# Page_2.net
KiCad netlist of a schematic drawn in Altium Designer
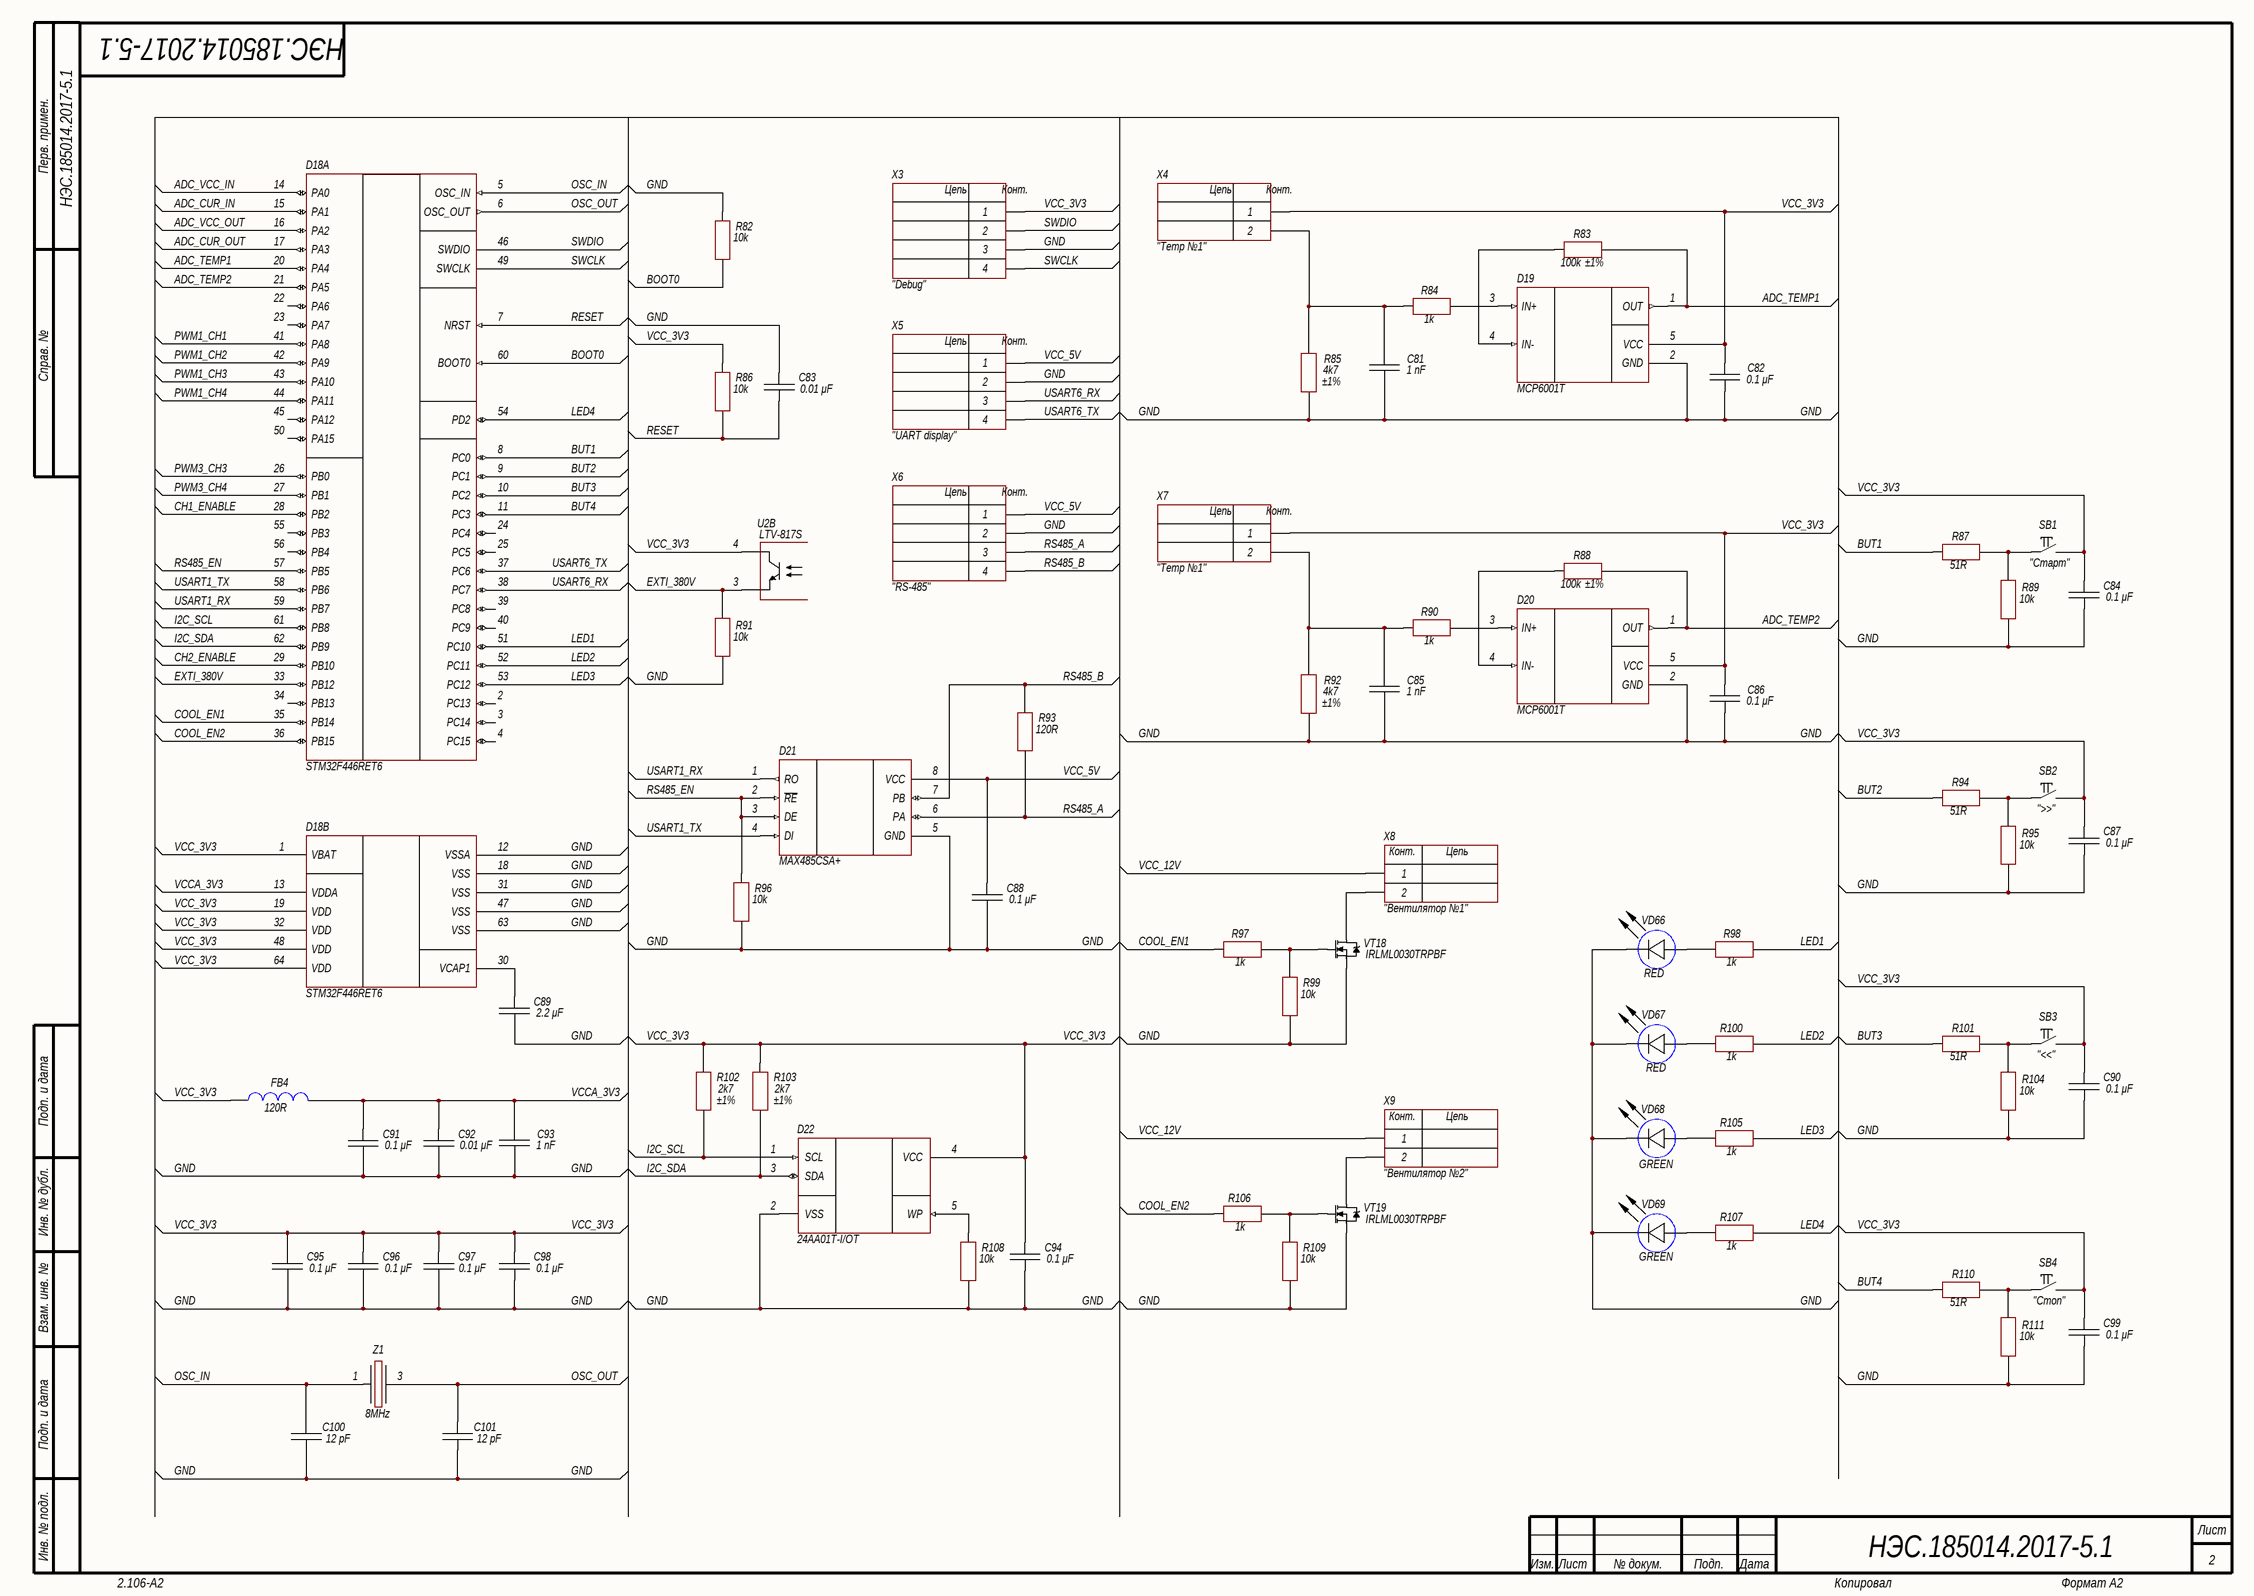
[diagram p0: Page 2.SchDoc]

(export (version "E")
  (design (tool "Eeschema 10.0.6"))
  (components
    (comp (ref "C81")
      (value "1 nF")
      (footprint "CH0805C")
      (fields (field (name "MANUFACTURER") "Yageo"))
      (libsource (lib "Discrete") (part "Capacitor"))
    )
    (comp (ref "C82")
      (value "0.1 μF")
      (footprint "CH0805C")
      (fields (field (name "MANUFACTURER") "Yageo"))
      (libsource (lib "Discrete") (part "Capacitor"))
    )
    (comp (ref "C83")
      (value "0.01 μF")
      (footprint "CH0805C")
      (fields (field (name "MANUFACTURER") "Yageo"))
      (libsource (lib "Discrete") (part "Capacitor"))
    )
    (comp (ref "C84")
      (value "0.1 μF")
      (footprint "CH0805C")
      (fields (field (name "MANUFACTURER") "Yageo"))
      (libsource (lib "Discrete") (part "Capacitor"))
    )
    (comp (ref "C85")
      (value "1 nF")
      (footprint "CH0805C")
      (fields (field (name "MANUFACTURER") "Yageo"))
      (libsource (lib "Discrete") (part "Capacitor"))
    )
    (comp (ref "C86")
      (value "0.1 μF")
      (footprint "CH0805C")
      (fields (field (name "MANUFACTURER") "Yageo"))
      (libsource (lib "Discrete") (part "Capacitor"))
    )
    (comp (ref "C87")
      (value "0.1 μF")
      (footprint "CH0805C")
      (fields (field (name "MANUFACTURER") "Yageo"))
      (libsource (lib "Discrete") (part "Capacitor"))
    )
    (comp (ref "C88")
      (value "0.1 μF")
      (footprint "CH0805C")
      (fields (field (name "MANUFACTURER") "Yageo"))
      (libsource (lib "Discrete") (part "Capacitor"))
    )
    (comp (ref "C89")
      (value "2.2 μF")
      (footprint "CH0805C")
      (fields (field (name "MANUFACTURER") "Yageo"))
      (libsource (lib "Discrete") (part "Capacitor"))
    )
    (comp (ref "C90")
      (value "0.1 μF")
      (footprint "CH0805C")
      (fields (field (name "MANUFACTURER") "Yageo"))
      (libsource (lib "Discrete") (part "Capacitor"))
    )
    (comp (ref "C91")
      (value "0.1 μF")
      (footprint "CH0805C")
      (fields (field (name "MANUFACTURER") "Yageo"))
      (libsource (lib "Discrete") (part "Capacitor"))
    )
    (comp (ref "C92")
      (value "0.01 μF")
      (footprint "CH0805C")
      (fields (field (name "MANUFACTURER") "Yageo"))
      (libsource (lib "Discrete") (part "Capacitor"))
    )
    (comp (ref "C93")
      (value "1 nF")
      (footprint "CH0805C")
      (fields (field (name "MANUFACTURER") "Yageo"))
      (libsource (lib "Discrete") (part "Capacitor"))
    )
    (comp (ref "C94")
      (value "0.1 μF")
      (footprint "CH0805C")
      (fields (field (name "MANUFACTURER") "Yageo"))
      (libsource (lib "Discrete") (part "Capacitor"))
    )
    (comp (ref "C95")
      (value "0.1 μF")
      (footprint "CH0805C")
      (fields (field (name "MANUFACTURER") "Yageo"))
      (libsource (lib "Discrete") (part "Capacitor"))
    )
    (comp (ref "C96")
      (value "0.1 μF")
      (footprint "CH0805C")
      (fields (field (name "MANUFACTURER") "Yageo"))
      (libsource (lib "Discrete") (part "Capacitor"))
    )
    (comp (ref "C97")
      (value "0.1 μF")
      (footprint "CH0805C")
      (fields (field (name "MANUFACTURER") "Yageo"))
      (libsource (lib "Discrete") (part "Capacitor"))
    )
    (comp (ref "C98")
      (value "0.1 μF")
      (footprint "CH0805C")
      (fields (field (name "MANUFACTURER") "Yageo"))
      (libsource (lib "Discrete") (part "Capacitor"))
    )
    (comp (ref "C99")
      (value "0.1 μF")
      (footprint "CH0805C")
      (fields (field (name "MANUFACTURER") "Yageo"))
      (libsource (lib "Discrete") (part "Capacitor"))
    )
    (comp (ref "C100")
      (value "12 pF")
      (footprint "CH0805C")
      (fields (field (name "MANUFACTURER") "Yageo"))
      (libsource (lib "Discrete") (part "Capacitor"))
    )
    (comp (ref "C101")
      (value "12 pF")
      (footprint "CH0805C")
      (fields (field (name "MANUFACTURER") "Yageo"))
      (libsource (lib "Discrete") (part "Capacitor"))
    )
    (comp (ref "D18")
      (value "STM32F446RET6")
      (footprint "64-LQFP")
      (description "Cortex-M4")
      (fields (field (name "MANUFACTURER") "STMicroelectronics"))
      (libsource (lib "Digital") (part "STM32F446RET6"))
    )
    (comp (ref "D19")
      (value "MCP6001T")
      (footprint "SOT23-5")
      (description "OP amplifier")
      (fields (field (name "MANUFACTURER") "Microchip Technology"))
      (libsource (lib "Analog") (part "MCP6001T"))
    )
    (comp (ref "D20")
      (value "MCP6001T")
      (footprint "SOT23-5")
      (description "OP amplifier")
      (fields (field (name "MANUFACTURER") "Microchip Technology"))
      (libsource (lib "Analog") (part "MCP6001T"))
    )
    (comp (ref "D21")
      (value "MAX485CSA+")
      (footprint "8-SOIC")
      (description "RS485")
      (fields (field (name "MANUFACTURER") "Maxim Integrated"))
      (libsource (lib "Interface") (part "MAX485CSA+"))
    )
    (comp (ref "D22")
      (value "24AA01T-I/OT")
      (footprint "SOT23-5")
      (description "EEPROM")
      (fields (field (name "MANUFACTURER") "Microchip Technology"))
      (libsource (lib "Digital") (part "24AA01T-I/OT"))
    )
    (comp (ref "FB4")
      (value "120R")
      (footprint "CH0805L")
      (fields (field (name "MANUFACTURER") "Murata Electronics North America"))
      (libsource (lib "Discrete") (part "Inductor"))
    )
    (comp (ref "R82")
      (value "10k")
      (footprint "CH0805R")
      (fields (field (name "MANUFACTURER") "Yageo"))
      (libsource (lib "Discrete") (part "Resistor"))
    )
    (comp (ref "R83")
      (value "100k")
      (footprint "CH0805R")
      (fields (field (name "MANUFACTURER") "Yageo") (field (name "COMPONENTKIND") "±1%"))
      (libsource (lib "") (part "Resistor_2"))
    )
    (comp (ref "R84")
      (value "1k")
      (footprint "CH0805R")
      (fields (field (name "MANUFACTURER") "Yageo"))
      (libsource (lib "") (part "Resistor_1"))
    )
    (comp (ref "R85")
      (value "4k7")
      (footprint "CH0805R")
      (fields (field (name "MANUFACTURER") "Yageo") (field (name "COMPONENTKIND") "±1%"))
      (libsource (lib "Discrete") (part "Resistor"))
    )
    (comp (ref "R86")
      (value "10k")
      (footprint "CH0805R")
      (fields (field (name "MANUFACTURER") "Yageo"))
      (libsource (lib "Discrete") (part "Resistor"))
    )
    (comp (ref "R87")
      (value "51R")
      (footprint "CH0805R")
      (fields (field (name "MANUFACTURER") "Yageo"))
      (libsource (lib "") (part "Resistor_3"))
    )
    (comp (ref "R88")
      (value "100k")
      (footprint "CH0805R")
      (fields (field (name "MANUFACTURER") "Yageo") (field (name "COMPONENTKIND") "±1%"))
      (libsource (lib "") (part "Resistor_2"))
    )
    (comp (ref "R89")
      (value "10k")
      (footprint "CH0805R")
      (fields (field (name "MANUFACTURER") "Yageo"))
      (libsource (lib "Discrete") (part "Resistor"))
    )
    (comp (ref "R90")
      (value "1k")
      (footprint "CH0805R")
      (fields (field (name "MANUFACTURER") "Yageo"))
      (libsource (lib "") (part "Resistor_1"))
    )
    (comp (ref "R91")
      (value "10k")
      (footprint "CH0805R")
      (fields (field (name "MANUFACTURER") "Yageo"))
      (libsource (lib "Discrete") (part "Resistor"))
    )
    (comp (ref "R92")
      (value "4k7")
      (footprint "CH0805R")
      (fields (field (name "MANUFACTURER") "Yageo") (field (name "COMPONENTKIND") "±1%"))
      (libsource (lib "Discrete") (part "Resistor"))
    )
    (comp (ref "R93")
      (value "120R")
      (footprint "CH0805R")
      (fields (field (name "MANUFACTURER") "Yageo"))
      (libsource (lib "Discrete") (part "Resistor"))
    )
    (comp (ref "R94")
      (value "51R")
      (footprint "CH0805R")
      (fields (field (name "MANUFACTURER") "Yageo"))
      (libsource (lib "") (part "Resistor_3"))
    )
    (comp (ref "R95")
      (value "10k")
      (footprint "CH0805R")
      (fields (field (name "MANUFACTURER") "Yageo"))
      (libsource (lib "Discrete") (part "Resistor"))
    )
    (comp (ref "R96")
      (value "10k")
      (footprint "CH0805R")
      (fields (field (name "MANUFACTURER") "Yageo"))
      (libsource (lib "Discrete") (part "Resistor"))
    )
    (comp (ref "R97")
      (value "1k")
      (footprint "CH0805R")
      (fields (field (name "MANUFACTURER") "Yageo"))
      (libsource (lib "") (part "Resistor_1"))
    )
    (comp (ref "R98")
      (value "1k")
      (footprint "CH0805R")
      (fields (field (name "MANUFACTURER") "Yageo"))
      (libsource (lib "") (part "Resistor_1"))
    )
    (comp (ref "R99")
      (value "10k")
      (footprint "CH0805R")
      (fields (field (name "MANUFACTURER") "Yageo"))
      (libsource (lib "Discrete") (part "Resistor"))
    )
    (comp (ref "R100")
      (value "1k")
      (footprint "CH0805R")
      (fields (field (name "MANUFACTURER") "Yageo"))
      (libsource (lib "") (part "Resistor_1"))
    )
    (comp (ref "R101")
      (value "51R")
      (footprint "CH0805R")
      (fields (field (name "MANUFACTURER") "Yageo"))
      (libsource (lib "") (part "Resistor_3"))
    )
    (comp (ref "R102")
      (value "2k7")
      (footprint "CH0805R")
      (fields (field (name "MANUFACTURER") "Yageo") (field (name "COMPONENTKIND") "±1%"))
      (libsource (lib "") (part "Resistor_1"))
    )
    (comp (ref "R103")
      (value "2k7")
      (footprint "CH0805R")
      (fields (field (name "MANUFACTURER") "Yageo") (field (name "COMPONENTKIND") "±1%"))
      (libsource (lib "") (part "Resistor_1"))
    )
    (comp (ref "R104")
      (value "10k")
      (footprint "CH0805R")
      (fields (field (name "MANUFACTURER") "Yageo"))
      (libsource (lib "Discrete") (part "Resistor"))
    )
    (comp (ref "R105")
      (value "1k")
      (footprint "CH0805R")
      (fields (field (name "MANUFACTURER") "Yageo"))
      (libsource (lib "") (part "Resistor_1"))
    )
    (comp (ref "R106")
      (value "1k")
      (footprint "CH0805R")
      (fields (field (name "MANUFACTURER") "Yageo"))
      (libsource (lib "") (part "Resistor_1"))
    )
    (comp (ref "R107")
      (value "1k")
      (footprint "CH0805R")
      (fields (field (name "MANUFACTURER") "Yageo"))
      (libsource (lib "") (part "Resistor_1"))
    )
    (comp (ref "R108")
      (value "10k")
      (footprint "CH0805R")
      (fields (field (name "MANUFACTURER") "Yageo"))
      (libsource (lib "Discrete") (part "Resistor"))
    )
    (comp (ref "R109")
      (value "10k")
      (footprint "CH0805R")
      (fields (field (name "MANUFACTURER") "Yageo"))
      (libsource (lib "Discrete") (part "Resistor"))
    )
    (comp (ref "R110")
      (value "51R")
      (footprint "CH0805R")
      (fields (field (name "MANUFACTURER") "Yageo"))
      (libsource (lib "") (part "Resistor_3"))
    )
    (comp (ref "R111")
      (value "10k")
      (footprint "CH0805R")
      (fields (field (name "MANUFACTURER") "Yageo"))
      (libsource (lib "Discrete") (part "Resistor"))
    )
    (comp (ref "SB1")
      (value "\"Старт\"")
      (footprint "BUT: 6x6 SMD")
      (description "6x6 mm")
      (fields (field (name "MANUFACTURER") "KLS"))
      (libsource (lib "Connectors") (part "Tactile switches"))
    )
    (comp (ref "SB2")
      (value "\">>\"")
      (footprint "BUT: 6x6 SMD")
      (description "6x6 mm")
      (fields (field (name "MANUFACTURER") "KLS"))
      (libsource (lib "Connectors") (part "Tactile switches"))
    )
    (comp (ref "SB3")
      (value "\"<<\"")
      (footprint "BUT: 6x6 SMD")
      (description "6x6 mm")
      (fields (field (name "MANUFACTURER") "KLS"))
      (libsource (lib "Connectors") (part "Tactile switches"))
    )
    (comp (ref "SB4")
      (value "\"Стоп\"")
      (footprint "BUT: 6x6 SMD")
      (description "6x6 mm")
      (fields (field (name "MANUFACTURER") "KLS"))
      (libsource (lib "Connectors") (part "Tactile switches"))
    )
    (comp (ref "U2")
      (value "LTV-817S")
      (footprint "4-SMD")
      (fields (field (name "MANUFACTURER") "Lite-On Inc."))
      (libsource (lib "Discrete") (part "Optoisolator"))
    )
    (comp (ref "VD66")
      (value "RED")
      (footprint "CH0805LR")
      (fields (field (name "MANUFACTURER") "Lite-On Inc."))
      (libsource (lib "Discrete") (part "LED"))
    )
    (comp (ref "VD67")
      (value "RED")
      (footprint "CH0805LR")
      (fields (field (name "MANUFACTURER") "Lite-On Inc."))
      (libsource (lib "Discrete") (part "LED"))
    )
    (comp (ref "VD68")
      (value "GREEN")
      (footprint "CH0805LG")
      (fields (field (name "MANUFACTURER") "Lite-On Inc."))
      (libsource (lib "Discrete") (part "LED"))
    )
    (comp (ref "VD69")
      (value "GREEN")
      (footprint "CH0805LG")
      (fields (field (name "MANUFACTURER") "Lite-On Inc."))
      (libsource (lib "Discrete") (part "LED"))
    )
    (comp (ref "VT18")
      (value "IRLML0030TRPBF")
      (footprint "SOT23_123")
      (description "Mosfet")
      (fields (field (name "MANUFACTURER") "Infineon Technologies"))
      (libsource (lib "Transistor") (part "N-chanel"))
    )
    (comp (ref "VT19")
      (value "IRLML0030TRPBF")
      (footprint "SOT23_123")
      (description "Mosfet")
      (fields (field (name "MANUFACTURER") "Infineon Technologies"))
      (libsource (lib "Transistor") (part "N-chanel"))
    )
    (comp (ref "X3")
      (value "\"Debug\"")
      (footprint "CON: PLD-4")
      (libsource (lib "Connectors") (part "4-Connector"))
    )
    (comp (ref "X4")
      (value "\"Temp №1\"")
      (footprint "CON: WF-02")
      (libsource (lib "") (part "2-Connector_1"))
    )
    (comp (ref "X5")
      (value "\"UART display\"")
      (footprint "CON: WF-04")
      (libsource (lib "Connectors") (part "4-Connector"))
    )
    (comp (ref "X6")
      (value "\"RS-485\"")
      (footprint "CON: WF-04")
      (libsource (lib "Connectors") (part "4-Connector"))
    )
    (comp (ref "X7")
      (value "\"Temp №1\"")
      (footprint "CON: WF-02")
      (libsource (lib "") (part "2-Connector_1"))
    )
    (comp (ref "X8")
      (value "\"Вентилятор №1\"")
      (footprint "CON: WF-02")
      (libsource (lib "Connectors") (part "2-Connector"))
    )
    (comp (ref "X9")
      (value "\"Вентилятор №2\"")
      (footprint "CON: WF-02")
      (libsource (lib "Connectors") (part "2-Connector"))
    )
    (comp (ref "Z1")
      (value "8MHz")
      (footprint "OSC: 5032")
      (fields (field (name "MANUFACTURER") "Geyer"))
      (libsource (lib "Discrete") (part "Oscillator"))
    )
  )
  (nets
    (net (code "1") (name "/ADC_CUR_IN") (class "Default")
      (node (ref "D18") (pin "15") (pinfunction "PA1_15") (pintype "bidirectional"))
    )
    (net (code "2") (name "/ADC_CUR_OUT") (class "Default")
      (node (ref "D18") (pin "17") (pinfunction "PA3_17") (pintype "bidirectional"))
    )
    (net (code "3") (name "/ADC_TEMP1") (class "Default")
      (node (ref "D18") (pin "20") (pinfunction "PA4_20") (pintype "bidirectional"))
      (node (ref "D19") (pin "1") (pinfunction "OUT_1") (pintype "output"))
      (node (ref "R83") (pin "2") (pinfunction "2_2") (pintype "passive"))
    )
    (net (code "4") (name "/ADC_TEMP2") (class "Default")
      (node (ref "D18") (pin "21") (pinfunction "PA5_21") (pintype "bidirectional"))
      (node (ref "D20") (pin "1") (pinfunction "OUT_1") (pintype "output"))
      (node (ref "R88") (pin "2") (pinfunction "2_2") (pintype "passive"))
    )
    (net (code "5") (name "/ADC_VCC_IN") (class "Default")
      (node (ref "D18") (pin "14") (pinfunction "PA0_14") (pintype "bidirectional"))
    )
    (net (code "6") (name "/ADC_VCC_OUT") (class "Default")
      (node (ref "D18") (pin "16") (pinfunction "PA2_16") (pintype "bidirectional"))
    )
    (net (code "7") (name "/BOOT0") (class "Default")
      (node (ref "D18") (pin "60") (pinfunction "BOOT0_60") (pintype "input"))
      (node (ref "R82") (pin "1") (pinfunction "1_1") (pintype "passive"))
    )
    (net (code "8") (name "/BUT1") (class "Default")
      (node (ref "D18") (pin "8") (pinfunction "PC0_8") (pintype "bidirectional"))
      (node (ref "R87") (pin "2") (pinfunction "2_2") (pintype "passive"))
    )
    (net (code "9") (name "/BUT2") (class "Default")
      (node (ref "D18") (pin "9") (pinfunction "PC1_9") (pintype "bidirectional"))
      (node (ref "R94") (pin "2") (pinfunction "2_2") (pintype "passive"))
    )
    (net (code "10") (name "/BUT3") (class "Default")
      (node (ref "D18") (pin "10") (pinfunction "PC2_10") (pintype "bidirectional"))
      (node (ref "R101") (pin "2") (pinfunction "2_2") (pintype "passive"))
    )
    (net (code "11") (name "/BUT4") (class "Default")
      (node (ref "D18") (pin "11") (pinfunction "PC3_11") (pintype "bidirectional"))
      (node (ref "R110") (pin "2") (pinfunction "2_2") (pintype "passive"))
    )
    (net (code "12") (name "/CH1_ENABLE") (class "Default")
      (node (ref "D18") (pin "28") (pinfunction "PB2_28") (pintype "bidirectional"))
    )
    (net (code "13") (name "/CH2_ENABLE") (class "Default")
      (node (ref "D18") (pin "29") (pinfunction "PB10_29") (pintype "bidirectional"))
    )
    (net (code "14") (name "/COOL_EN1") (class "Default")
      (node (ref "D18") (pin "35") (pinfunction "PB14_35") (pintype "bidirectional"))
      (node (ref "R97") (pin "2") (pinfunction "2_2") (pintype "passive"))
    )
    (net (code "15") (name "/COOL_EN2") (class "Default")
      (node (ref "D18") (pin "36") (pinfunction "PB15_36") (pintype "bidirectional"))
      (node (ref "R106") (pin "2") (pinfunction "2_2") (pintype "passive"))
    )
    (net (code "16") (name "/EXTI_380V") (class "Default")
      (node (ref "D18") (pin "33") (pinfunction "PB12_33") (pintype "bidirectional"))
      (node (ref "R91") (pin "2") (pinfunction "2_2") (pintype "passive"))
      (node (ref "U2") (pin "3") (pinfunction "E_3") (pintype "passive"))
    )
    (net (code "17") (name "/GND") (class "Default")
      (node (ref "C100") (pin "1") (pinfunction "1_1") (pintype "power_in"))
      (node (ref "C101") (pin "1") (pinfunction "1_1") (pintype "power_in"))
      (node (ref "C81") (pin "1") (pinfunction "1_1") (pintype "power_in"))
      (node (ref "C82") (pin "1") (pinfunction "1_1") (pintype "power_in"))
      (node (ref "C83") (pin "2") (pinfunction "2_2") (pintype "power_in"))
      (node (ref "C84") (pin "1") (pinfunction "1_1") (pintype "power_in"))
      (node (ref "C85") (pin "1") (pinfunction "1_1") (pintype "power_in"))
      (node (ref "C86") (pin "1") (pinfunction "1_1") (pintype "power_in"))
      (node (ref "C87") (pin "1") (pinfunction "1_1") (pintype "power_in"))
      (node (ref "C88") (pin "1") (pinfunction "1_1") (pintype "power_in"))
      (node (ref "C89") (pin "1") (pinfunction "1_1") (pintype "power_in"))
      (node (ref "C90") (pin "1") (pinfunction "1_1") (pintype "power_in"))
      (node (ref "C91") (pin "1") (pinfunction "1_1") (pintype "power_in"))
      (node (ref "C92") (pin "1") (pinfunction "1_1") (pintype "power_in"))
      (node (ref "C93") (pin "1") (pinfunction "1_1") (pintype "power_in"))
      (node (ref "C94") (pin "1") (pinfunction "1_1") (pintype "power_in"))
      (node (ref "C95") (pin "1") (pinfunction "1_1") (pintype "power_in"))
      (node (ref "C96") (pin "1") (pinfunction "1_1") (pintype "power_in"))
      (node (ref "C97") (pin "1") (pinfunction "1_1") (pintype "power_in"))
      (node (ref "C98") (pin "1") (pinfunction "1_1") (pintype "power_in"))
      (node (ref "C99") (pin "1") (pinfunction "1_1") (pintype "power_in"))
      (node (ref "D18") (pin "12") (pinfunction "VSSA_12") (pintype "passive"))
      (node (ref "D18") (pin "18") (pinfunction "VSS_18") (pintype "passive"))
      (node (ref "D18") (pin "31") (pinfunction "VSS_31") (pintype "passive"))
      (node (ref "D18") (pin "47") (pinfunction "VSS_47") (pintype "passive"))
      (node (ref "D18") (pin "63") (pinfunction "VSS_63") (pintype "passive"))
      (node (ref "D19") (pin "2") (pinfunction "GND_2") (pintype "power_in"))
      (node (ref "D20") (pin "2") (pinfunction "GND_2") (pintype "power_in"))
      (node (ref "D21") (pin "5") (pinfunction "GND_5") (pintype "power_in"))
      (node (ref "D22") (pin "2") (pinfunction "VSS_2") (pintype "power_in"))
      (node (ref "R104") (pin "1") (pinfunction "1_1") (pintype "passive"))
      (node (ref "R108") (pin "1") (pinfunction "1_1") (pintype "passive"))
      (node (ref "R109") (pin "1") (pinfunction "1_1") (pintype "passive"))
      (node (ref "R111") (pin "1") (pinfunction "1_1") (pintype "passive"))
      (node (ref "R82") (pin "2") (pinfunction "2_2") (pintype "passive"))
      (node (ref "R85") (pin "1") (pinfunction "1_1") (pintype "passive"))
      (node (ref "R89") (pin "1") (pinfunction "1_1") (pintype "passive"))
      (node (ref "R91") (pin "1") (pinfunction "1_1") (pintype "passive"))
      (node (ref "R92") (pin "1") (pinfunction "1_1") (pintype "passive"))
      (node (ref "R95") (pin "1") (pinfunction "1_1") (pintype "passive"))
      (node (ref "R96") (pin "1") (pinfunction "1_1") (pintype "passive"))
      (node (ref "R99") (pin "1") (pinfunction "1_1") (pintype "passive"))
      (node (ref "VD66") (pin "2") (pinfunction "C_2") (pintype "passive"))
      (node (ref "VD67") (pin "2") (pinfunction "C_2") (pintype "passive"))
      (node (ref "VD68") (pin "2") (pinfunction "C_2") (pintype "passive"))
      (node (ref "VD69") (pin "2") (pinfunction "C_2") (pintype "passive"))
      (node (ref "VT18") (pin "3") (pinfunction "S_3") (pintype "passive"))
      (node (ref "VT19") (pin "3") (pinfunction "S_3") (pintype "passive"))
      (node (ref "X3") (pin "3") (pinfunction "3_3") (pintype "power_in"))
      (node (ref "X5") (pin "2") (pinfunction "2_2") (pintype "passive"))
      (node (ref "X6") (pin "2") (pinfunction "2_2") (pintype "passive"))
    )
    (net (code "18") (name "/I2C_SCL") (class "Default")
      (node (ref "D18") (pin "61") (pinfunction "PB8_61") (pintype "bidirectional"))
      (node (ref "D22") (pin "1") (pinfunction "SCL_1") (pintype "input"))
      (node (ref "R102") (pin "2") (pinfunction "2_2") (pintype "passive"))
    )
    (net (code "19") (name "/I2C_SDA") (class "Default")
      (node (ref "D18") (pin "62") (pinfunction "PB9_62") (pintype "bidirectional"))
      (node (ref "D22") (pin "3") (pinfunction "SDA_3") (pintype "bidirectional"))
      (node (ref "R103") (pin "2") (pinfunction "2_2") (pintype "passive"))
    )
    (net (code "20") (name "/LED1") (class "Default")
      (node (ref "D18") (pin "51") (pinfunction "PC10_51") (pintype "bidirectional"))
      (node (ref "R98") (pin "1") (pinfunction "1_1") (pintype "passive"))
    )
    (net (code "21") (name "/LED2") (class "Default")
      (node (ref "D18") (pin "52") (pinfunction "PC11_52") (pintype "bidirectional"))
      (node (ref "R100") (pin "1") (pinfunction "1_1") (pintype "passive"))
    )
    (net (code "22") (name "/LED3") (class "Default")
      (node (ref "D18") (pin "53") (pinfunction "PC12_53") (pintype "bidirectional"))
      (node (ref "R105") (pin "1") (pinfunction "1_1") (pintype "passive"))
    )
    (net (code "23") (name "/LED4") (class "Default")
      (node (ref "D18") (pin "54") (pinfunction "PD2_54") (pintype "bidirectional"))
      (node (ref "R107") (pin "1") (pinfunction "1_1") (pintype "passive"))
    )
    (net (code "24") (name "/OSC_IN") (class "Default")
      (node (ref "C100") (pin "2") (pinfunction "2_2") (pintype "power_in"))
      (node (ref "D18") (pin "5") (pinfunction "OSC_IN_5") (pintype "input"))
      (node (ref "Z1") (pin "1") (pinfunction "1_1") (pintype "passive"))
    )
    (net (code "25") (name "/OSC_OUT") (class "Default")
      (node (ref "C101") (pin "2") (pinfunction "2_2") (pintype "power_in"))
      (node (ref "D18") (pin "6") (pinfunction "OSC_OUT_6") (pintype "output"))
      (node (ref "Z1") (pin "3") (pinfunction "3_3") (pintype "passive"))
    )
    (net (code "26") (name "/PWM1_CH1") (class "Default")
      (node (ref "D18") (pin "41") (pinfunction "PA8_41") (pintype "bidirectional"))
    )
    (net (code "27") (name "/PWM1_CH2") (class "Default")
      (node (ref "D18") (pin "42") (pinfunction "PA9_42") (pintype "bidirectional"))
    )
    (net (code "28") (name "/PWM1_CH3") (class "Default")
      (node (ref "D18") (pin "43") (pinfunction "PA10_43") (pintype "bidirectional"))
    )
    (net (code "29") (name "/PWM1_CH4") (class "Default")
      (node (ref "D18") (pin "44") (pinfunction "PA11_44") (pintype "bidirectional"))
    )
    (net (code "30") (name "/PWM3_CH3") (class "Default")
      (node (ref "D18") (pin "26") (pinfunction "PB0_26") (pintype "bidirectional"))
    )
    (net (code "31") (name "/PWM3_CH4") (class "Default")
      (node (ref "D18") (pin "27") (pinfunction "PB1_27") (pintype "bidirectional"))
    )
    (net (code "32") (name "/RESET") (class "Default")
      (node (ref "C83") (pin "1") (pinfunction "1_1") (pintype "power_in"))
      (node (ref "D18") (pin "7") (pinfunction "NRST_7") (pintype "input"))
      (node (ref "R86") (pin "1") (pinfunction "1_1") (pintype "passive"))
    )
    (net (code "33") (name "/RS485_A") (class "Default")
      (node (ref "D21") (pin "6") (pinfunction "PA_6") (pintype "bidirectional"))
      (node (ref "R93") (pin "1") (pinfunction "1_1") (pintype "passive"))
      (node (ref "X6") (pin "3") (pinfunction "3_3") (pintype "power_in"))
    )
    (net (code "34") (name "/RS485_B") (class "Default")
      (node (ref "D21") (pin "7") (pinfunction "PB_7") (pintype "bidirectional"))
      (node (ref "R93") (pin "2") (pinfunction "2_2") (pintype "passive"))
      (node (ref "X6") (pin "4") (pinfunction "4_4") (pintype "power_in"))
    )
    (net (code "35") (name "/RS485_EN") (class "Default")
      (node (ref "D18") (pin "57") (pinfunction "PB5_57") (pintype "bidirectional"))
      (node (ref "D21") (pin "2") (pinfunction "~{RE}_2") (pintype "input"))
      (node (ref "D21") (pin "3") (pinfunction "DE_3") (pintype "input"))
      (node (ref "R96") (pin "2") (pinfunction "2_2") (pintype "passive"))
    )
    (net (code "36") (name "/SWCLK") (class "Default")
      (node (ref "D18") (pin "49") (pinfunction "SWCLK_49") (pintype "passive"))
      (node (ref "X3") (pin "4") (pinfunction "4_4") (pintype "power_in"))
    )
    (net (code "37") (name "/SWDIO") (class "Default")
      (node (ref "D18") (pin "46") (pinfunction "SWDIO_46") (pintype "passive"))
      (node (ref "X3") (pin "2") (pinfunction "2_2") (pintype "passive"))
    )
    (net (code "38") (name "/USART1_RX") (class "Default")
      (node (ref "D18") (pin "59") (pinfunction "PB7_59") (pintype "bidirectional"))
      (node (ref "D21") (pin "1") (pinfunction "RO_1") (pintype "output"))
    )
    (net (code "39") (name "/USART1_TX") (class "Default")
      (node (ref "D18") (pin "58") (pinfunction "PB6_58") (pintype "bidirectional"))
      (node (ref "D21") (pin "4") (pinfunction "DI_4") (pintype "input"))
    )
    (net (code "40") (name "/USART6_RX") (class "Default")
      (node (ref "D18") (pin "38") (pinfunction "PC7_38") (pintype "bidirectional"))
      (node (ref "X5") (pin "3") (pinfunction "3_3") (pintype "power_in"))
    )
    (net (code "41") (name "/USART6_TX") (class "Default")
      (node (ref "D18") (pin "37") (pinfunction "PC6_37") (pintype "bidirectional"))
      (node (ref "X5") (pin "4") (pinfunction "4_4") (pintype "power_in"))
    )
    (net (code "42") (name "/VCCA_3V3") (class "Default")
      (node (ref "C91") (pin "2") (pinfunction "2_2") (pintype "power_in"))
      (node (ref "C92") (pin "2") (pinfunction "2_2") (pintype "power_in"))
      (node (ref "C93") (pin "2") (pinfunction "2_2") (pintype "power_in"))
      (node (ref "D18") (pin "13") (pinfunction "VDDA_13") (pintype "passive"))
      (node (ref "FB4") (pin "1") (pinfunction "1_1") (pintype "passive"))
    )
    (net (code "43") (name "/VCC_3V3") (class "Default")
      (node (ref "C82") (pin "2") (pinfunction "2_2") (pintype "power_in"))
      (node (ref "C84") (pin "2") (pinfunction "2_2") (pintype "power_in"))
      (node (ref "C86") (pin "2") (pinfunction "2_2") (pintype "power_in"))
      (node (ref "C87") (pin "2") (pinfunction "2_2") (pintype "power_in"))
      (node (ref "C90") (pin "2") (pinfunction "2_2") (pintype "power_in"))
      (node (ref "C94") (pin "2") (pinfunction "2_2") (pintype "power_in"))
      (node (ref "C95") (pin "2") (pinfunction "2_2") (pintype "power_in"))
      (node (ref "C96") (pin "2") (pinfunction "2_2") (pintype "power_in"))
      (node (ref "C97") (pin "2") (pinfunction "2_2") (pintype "power_in"))
      (node (ref "C98") (pin "2") (pinfunction "2_2") (pintype "power_in"))
      (node (ref "C99") (pin "2") (pinfunction "2_2") (pintype "power_in"))
      (node (ref "D18") (pin "1") (pinfunction "VBAT_1") (pintype "passive"))
      (node (ref "D18") (pin "19") (pinfunction "VDD_19") (pintype "passive"))
      (node (ref "D18") (pin "32") (pinfunction "VDD_32") (pintype "passive"))
      (node (ref "D18") (pin "48") (pinfunction "VDD_48") (pintype "passive"))
      (node (ref "D18") (pin "64") (pinfunction "VDD_64") (pintype "passive"))
      (node (ref "D19") (pin "5") (pinfunction "VCC_5") (pintype "power_in"))
      (node (ref "D20") (pin "5") (pinfunction "VCC_5") (pintype "power_in"))
      (node (ref "D22") (pin "4") (pinfunction "VCC_4") (pintype "power_in"))
      (node (ref "FB4") (pin "2") (pinfunction "2_2") (pintype "passive"))
      (node (ref "R102") (pin "1") (pinfunction "1_1") (pintype "passive"))
      (node (ref "R103") (pin "1") (pinfunction "1_1") (pintype "passive"))
      (node (ref "R86") (pin "2") (pinfunction "2_2") (pintype "passive"))
      (node (ref "SB1") (pin "2") (pinfunction "2_2") (pintype "passive"))
      (node (ref "SB2") (pin "2") (pinfunction "2_2") (pintype "passive"))
      (node (ref "SB3") (pin "2") (pinfunction "2_2") (pintype "passive"))
      (node (ref "SB4") (pin "2") (pinfunction "2_2") (pintype "passive"))
      (node (ref "U2") (pin "4") (pinfunction "C_4") (pintype "passive"))
      (node (ref "X3") (pin "1") (pinfunction "1_1") (pintype "passive"))
      (node (ref "X4") (pin "1") (pinfunction "1_1") (pintype "passive"))
      (node (ref "X7") (pin "1") (pinfunction "1_1") (pintype "passive"))
    )
    (net (code "44") (name "/VCC_5V") (class "Default")
      (node (ref "C88") (pin "2") (pinfunction "2_2") (pintype "power_in"))
      (node (ref "D21") (pin "8") (pinfunction "VCC_8") (pintype "power_in"))
      (node (ref "X5") (pin "1") (pinfunction "1_1") (pintype "passive"))
      (node (ref "X6") (pin "1") (pinfunction "1_1") (pintype "passive"))
    )
    (net (code "45") (name "/VCC_12V") (class "Default")
      (node (ref "X8") (pin "1") (pinfunction "1_1") (pintype "passive"))
      (node (ref "X9") (pin "1") (pinfunction "1_1") (pintype "passive"))
    )
    (net (code "46") (name "Net-(C81-Pad2)") (class "Default")
      (node (ref "C81") (pin "2") (pinfunction "2_2") (pintype "power_in"))
      (node (ref "R84") (pin "2") (pinfunction "2_2") (pintype "passive"))
      (node (ref "R85") (pin "2") (pinfunction "2_2") (pintype "passive"))
      (node (ref "X4") (pin "2") (pinfunction "2_2") (pintype "passive"))
    )
    (net (code "47") (name "Net-(C85-Pad2)") (class "Default")
      (node (ref "C85") (pin "2") (pinfunction "2_2") (pintype "power_in"))
      (node (ref "R90") (pin "2") (pinfunction "2_2") (pintype "passive"))
      (node (ref "R92") (pin "2") (pinfunction "2_2") (pintype "passive"))
      (node (ref "X7") (pin "2") (pinfunction "2_2") (pintype "passive"))
    )
    (net (code "48") (name "Net-(D18B-VCAP1)") (class "Default")
      (node (ref "C89") (pin "2") (pinfunction "2_2") (pintype "power_in"))
      (node (ref "D18") (pin "30") (pinfunction "VCAP1_30") (pintype "passive"))
    )
    (net (code "49") (name "Net-(D19-IN+)") (class "Default")
      (node (ref "D19") (pin "3") (pinfunction "IN+_3") (pintype "input"))
      (node (ref "R84") (pin "1") (pinfunction "1_1") (pintype "passive"))
    )
    (net (code "50") (name "Net-(D19-IN-)") (class "Default")
      (node (ref "D19") (pin "4") (pinfunction "IN-_4") (pintype "input"))
      (node (ref "R83") (pin "1") (pinfunction "1_1") (pintype "passive"))
    )
    (net (code "51") (name "Net-(D20-IN+)") (class "Default")
      (node (ref "D20") (pin "3") (pinfunction "IN+_3") (pintype "input"))
      (node (ref "R90") (pin "1") (pinfunction "1_1") (pintype "passive"))
    )
    (net (code "52") (name "Net-(D20-IN-)") (class "Default")
      (node (ref "D20") (pin "4") (pinfunction "IN-_4") (pintype "input"))
      (node (ref "R88") (pin "1") (pinfunction "1_1") (pintype "passive"))
    )
    (net (code "53") (name "Net-(D22-WP)") (class "Default")
      (node (ref "D22") (pin "5") (pinfunction "WP_5") (pintype "input"))
      (node (ref "R108") (pin "2") (pinfunction "2_2") (pintype "passive"))
    )
    (net (code "54") (name "Net-(R87-Pad1)") (class "Default")
      (node (ref "R87") (pin "1") (pinfunction "1_1") (pintype "passive"))
      (node (ref "R89") (pin "2") (pinfunction "2_2") (pintype "passive"))
      (node (ref "SB1") (pin "1") (pinfunction "1_1") (pintype "passive"))
    )
    (net (code "55") (name "Net-(R94-Pad1)") (class "Default")
      (node (ref "R94") (pin "1") (pinfunction "1_1") (pintype "passive"))
      (node (ref "R95") (pin "2") (pinfunction "2_2") (pintype "passive"))
      (node (ref "SB2") (pin "1") (pinfunction "1_1") (pintype "passive"))
    )
    (net (code "56") (name "Net-(R101-Pad1)") (class "Default")
      (node (ref "R101") (pin "1") (pinfunction "1_1") (pintype "passive"))
      (node (ref "R104") (pin "2") (pinfunction "2_2") (pintype "passive"))
      (node (ref "SB3") (pin "1") (pinfunction "1_1") (pintype "passive"))
    )
    (net (code "57") (name "Net-(R110-Pad1)") (class "Default")
      (node (ref "R110") (pin "1") (pinfunction "1_1") (pintype "passive"))
      (node (ref "R111") (pin "2") (pinfunction "2_2") (pintype "passive"))
      (node (ref "SB4") (pin "1") (pinfunction "1_1") (pintype "passive"))
    )
    (net (code "58") (name "Net-(VD66-A)") (class "Default")
      (node (ref "R98") (pin "2") (pinfunction "2_2") (pintype "passive"))
      (node (ref "VD66") (pin "1") (pinfunction "A_1") (pintype "passive"))
    )
    (net (code "59") (name "Net-(VD67-A)") (class "Default")
      (node (ref "R100") (pin "2") (pinfunction "2_2") (pintype "passive"))
      (node (ref "VD67") (pin "1") (pinfunction "A_1") (pintype "passive"))
    )
    (net (code "60") (name "Net-(VD68-A)") (class "Default")
      (node (ref "R105") (pin "2") (pinfunction "2_2") (pintype "passive"))
      (node (ref "VD68") (pin "1") (pinfunction "A_1") (pintype "passive"))
    )
    (net (code "61") (name "Net-(VD69-A)") (class "Default")
      (node (ref "R107") (pin "2") (pinfunction "2_2") (pintype "passive"))
      (node (ref "VD69") (pin "1") (pinfunction "A_1") (pintype "passive"))
    )
    (net (code "62") (name "Net-(VT18-D)") (class "Default")
      (node (ref "VT18") (pin "2") (pinfunction "D_2") (pintype "passive"))
      (node (ref "X8") (pin "2") (pinfunction "2_2") (pintype "passive"))
    )
    (net (code "63") (name "Net-(VT18-G)") (class "Default")
      (node (ref "R97") (pin "1") (pinfunction "1_1") (pintype "passive"))
      (node (ref "R99") (pin "2") (pinfunction "2_2") (pintype "passive"))
      (node (ref "VT18") (pin "1") (pinfunction "G_1") (pintype "passive"))
    )
    (net (code "64") (name "Net-(VT19-D)") (class "Default")
      (node (ref "VT19") (pin "2") (pinfunction "D_2") (pintype "passive"))
      (node (ref "X9") (pin "2") (pinfunction "2_2") (pintype "passive"))
    )
    (net (code "65") (name "Net-(VT19-G)") (class "Default")
      (node (ref "R106") (pin "1") (pinfunction "1_1") (pintype "passive"))
      (node (ref "R109") (pin "2") (pinfunction "2_2") (pintype "passive"))
      (node (ref "VT19") (pin "1") (pinfunction "G_1") (pintype "passive"))
    )
    (net (code "66") (name "unconnected-(D18A-PA6-Pad22)") (class "Default")
      (node (ref "D18") (pin "22") (pinfunction "PA6_22") (pintype "bidirectional"))
    )
    (net (code "67") (name "unconnected-(D18A-PA7-Pad23)") (class "Default")
      (node (ref "D18") (pin "23") (pinfunction "PA7_23") (pintype "bidirectional"))
    )
    (net (code "68") (name "unconnected-(D18A-PA12-Pad45)") (class "Default")
      (node (ref "D18") (pin "45") (pinfunction "PA12_45") (pintype "bidirectional"))
    )
    (net (code "69") (name "unconnected-(D18A-PA15-Pad50)") (class "Default")
      (node (ref "D18") (pin "50") (pinfunction "PA15_50") (pintype "bidirectional"))
    )
    (net (code "70") (name "unconnected-(D18A-PB3-Pad55)") (class "Default")
      (node (ref "D18") (pin "55") (pinfunction "PB3_55") (pintype "bidirectional"))
    )
    (net (code "71") (name "unconnected-(D18A-PB4-Pad56)") (class "Default")
      (node (ref "D18") (pin "56") (pinfunction "PB4_56") (pintype "bidirectional"))
    )
    (net (code "72") (name "unconnected-(D18A-PB13-Pad34)") (class "Default")
      (node (ref "D18") (pin "34") (pinfunction "PB13_34") (pintype "bidirectional"))
    )
    (net (code "73") (name "unconnected-(D18A-PC4-Pad24)") (class "Default")
      (node (ref "D18") (pin "24") (pinfunction "PC4_24") (pintype "bidirectional"))
    )
    (net (code "74") (name "unconnected-(D18A-PC5-Pad25)") (class "Default")
      (node (ref "D18") (pin "25") (pinfunction "PC5_25") (pintype "bidirectional"))
    )
    (net (code "75") (name "unconnected-(D18A-PC8-Pad39)") (class "Default")
      (node (ref "D18") (pin "39") (pinfunction "PC8_39") (pintype "bidirectional"))
    )
    (net (code "76") (name "unconnected-(D18A-PC9-Pad40)") (class "Default")
      (node (ref "D18") (pin "40") (pinfunction "PC9_40") (pintype "bidirectional"))
    )
    (net (code "77") (name "unconnected-(D18A-PC13-Pad2)") (class "Default")
      (node (ref "D18") (pin "2") (pinfunction "PC13_2") (pintype "bidirectional"))
    )
    (net (code "78") (name "unconnected-(D18A-PC14-Pad3)") (class "Default")
      (node (ref "D18") (pin "3") (pinfunction "PC14_3") (pintype "bidirectional"))
    )
    (net (code "79") (name "unconnected-(D18A-PC15-Pad4)") (class "Default")
      (node (ref "D18") (pin "4") (pinfunction "PC15_4") (pintype "bidirectional"))
    )
  )
)
